# PCB2_1_1.net
KiCad netlist of a schematic drawn in EAGLE
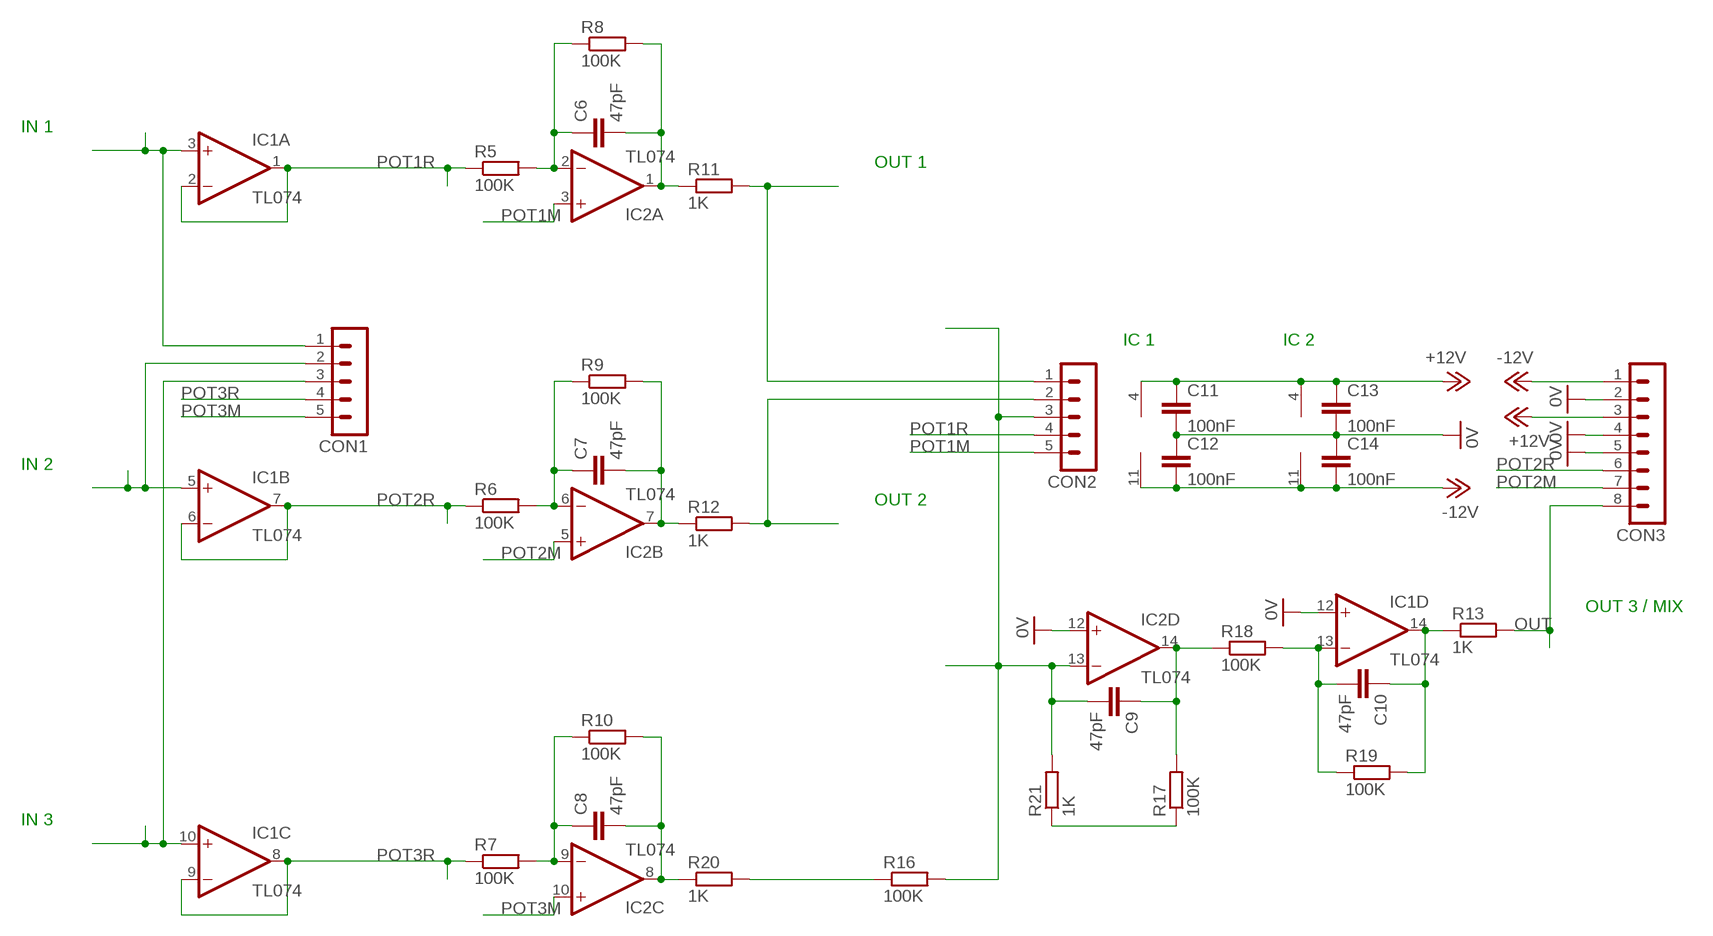
[diagram p0: schematic, sheet 1]

(export (version "E")
  (design (tool "Eeschema 10.0.6"))
  (components
    (comp (ref "C6")
      (value "47pF")
      (footprint "eagle-import:C025-024X044")
      (libsource (lib "eagle-import") (part "C-EU025-024X044"))
    )
    (comp (ref "C7")
      (value "47pF")
      (footprint "eagle-import:C025-024X044")
      (libsource (lib "eagle-import") (part "C-EU025-024X044"))
    )
    (comp (ref "C8")
      (value "47pF")
      (footprint "eagle-import:C025-024X044")
      (libsource (lib "eagle-import") (part "C-EU025-024X044"))
    )
    (comp (ref "C9")
      (value "47pF")
      (footprint "eagle-import:C025-024X044")
      (libsource (lib "eagle-import") (part "C-EU025-024X044"))
    )
    (comp (ref "C10")
      (value "47pF")
      (footprint "eagle-import:C025-024X044")
      (libsource (lib "eagle-import") (part "C-EU025-024X044"))
    )
    (comp (ref "C11")
      (value "100nF")
      (footprint "eagle-import:C025-024X044")
      (libsource (lib "eagle-import") (part "C-EU025-024X044"))
    )
    (comp (ref "C12")
      (value "100nF")
      (footprint "eagle-import:C025-024X044")
      (libsource (lib "eagle-import") (part "C-EU025-024X044"))
    )
    (comp (ref "C13")
      (value "100nF")
      (footprint "eagle-import:C025-024X044")
      (libsource (lib "eagle-import") (part "C-EU025-024X044"))
    )
    (comp (ref "C14")
      (value "100nF")
      (footprint "eagle-import:C025-024X044")
      (libsource (lib "eagle-import") (part "C-EU025-024X044"))
    )
    (comp (ref "CON1")
      (value "MA05-1")
      (footprint "eagle-import:MA05-1")
      (libsource (lib "eagle-import") (part "MA05-1"))
    )
    (comp (ref "CON2")
      (value "MA05-1")
      (footprint "eagle-import:MA05-1")
      (libsource (lib "eagle-import") (part "MA05-1"))
    )
    (comp (ref "CON3")
      (value "MA08-1")
      (footprint "eagle-import:MA08-1")
      (libsource (lib "eagle-import") (part "MA08-1"))
    )
    (comp (ref "IC1")
      (value "TL074")
      (footprint "eagle-import:DIL14")
      (libsource (lib "eagle-import") (part "TL074P"))
    )
    (comp (ref "IC2")
      (value "TL074")
      (footprint "eagle-import:DIL14")
      (libsource (lib "eagle-import") (part "TL074P"))
    )
    (comp (ref "R5")
      (value "100K")
      (footprint "eagle-import:0207_9")
      (libsource (lib "eagle-import") (part "R-EU_0207/10"))
    )
    (comp (ref "R6")
      (value "100K")
      (footprint "eagle-import:0207_9")
      (libsource (lib "eagle-import") (part "R-EU_0207/10"))
    )
    (comp (ref "R7")
      (value "100K")
      (footprint "eagle-import:0207_9")
      (libsource (lib "eagle-import") (part "R-EU_0207/10"))
    )
    (comp (ref "R8")
      (value "100K")
      (footprint "eagle-import:0207_9")
      (libsource (lib "eagle-import") (part "R-EU_0207/10"))
    )
    (comp (ref "R9")
      (value "100K")
      (footprint "eagle-import:0207_9")
      (libsource (lib "eagle-import") (part "R-EU_0207/10"))
    )
    (comp (ref "R10")
      (value "100K")
      (footprint "eagle-import:0207_9")
      (libsource (lib "eagle-import") (part "R-EU_0207/10"))
    )
    (comp (ref "R11")
      (value "1K")
      (footprint "eagle-import:0207_9")
      (libsource (lib "eagle-import") (part "R-EU_0207/10"))
    )
    (comp (ref "R12")
      (value "1K")
      (footprint "eagle-import:0207_9")
      (libsource (lib "eagle-import") (part "R-EU_0207/10"))
    )
    (comp (ref "R13")
      (value "1K")
      (footprint "eagle-import:0207_9")
      (libsource (lib "eagle-import") (part "R-EU_0207/10"))
    )
    (comp (ref "R16")
      (value "100K")
      (footprint "eagle-import:0207_9")
      (libsource (lib "eagle-import") (part "R-EU_0207/10"))
    )
    (comp (ref "R17")
      (value "100K")
      (footprint "eagle-import:0207_9")
      (libsource (lib "eagle-import") (part "R-EU_0207/10"))
    )
    (comp (ref "R18")
      (value "100K")
      (footprint "eagle-import:0207_9")
      (libsource (lib "eagle-import") (part "R-EU_0207/10"))
    )
    (comp (ref "R19")
      (value "100K")
      (footprint "eagle-import:0207_9")
      (libsource (lib "eagle-import") (part "R-EU_0207/10"))
    )
    (comp (ref "R20")
      (value "1K")
      (footprint "eagle-import:0207_9")
      (libsource (lib "eagle-import") (part "R-EU_0207/10"))
    )
    (comp (ref "R21")
      (value "1K")
      (footprint "eagle-import:0207_9")
      (libsource (lib "eagle-import") (part "R-EU_0207/10"))
    )
  )
  (nets
    (net (code "1") (name "+12V") (class "Default")
      (node (ref "C11") (pin "1") (pinfunction "1_1") (pintype "passive"))
      (node (ref "C13") (pin "1") (pinfunction "1_1") (pintype "passive"))
      (node (ref "CON3") (pin "3") (pinfunction "3_3") (pintype "passive"))
      (node (ref "IC1") (pin "4") (pinfunction "V+_4") (pintype "power_in"))
      (node (ref "IC2") (pin "4") (pinfunction "V+_4") (pintype "power_in"))
    )
    (net (code "2") (name "-12V") (class "Default")
      (node (ref "C12") (pin "2") (pinfunction "2_2") (pintype "passive"))
      (node (ref "C14") (pin "2") (pinfunction "2_2") (pintype "passive"))
      (node (ref "CON3") (pin "1") (pinfunction "1_1") (pintype "passive"))
      (node (ref "IC1") (pin "11") (pinfunction "V-_11") (pintype "power_in"))
      (node (ref "IC2") (pin "11") (pinfunction "V-_11") (pintype "power_in"))
    )
    (net (code "3") (name "/OUT") (class "Default")
      (node (ref "CON3") (pin "8") (pinfunction "8_8") (pintype "passive"))
      (node (ref "R13") (pin "2") (pinfunction "2_2") (pintype "passive"))
    )
    (net (code "4") (name "/POT1M") (class "Default")
      (node (ref "CON2") (pin "5") (pinfunction "5_5") (pintype "passive"))
      (node (ref "IC2") (pin "3") (pinfunction "+IN_3") (pintype "input"))
    )
    (net (code "5") (name "/POT1R") (class "Default")
      (node (ref "CON2") (pin "4") (pinfunction "4_4") (pintype "passive"))
      (node (ref "IC1") (pin "1") (pinfunction "OUT_1") (pintype "output"))
      (node (ref "IC1") (pin "2") (pinfunction "-IN_2") (pintype "input"))
      (node (ref "R5") (pin "1") (pinfunction "1_1") (pintype "passive"))
    )
    (net (code "6") (name "/POT2M") (class "Default")
      (node (ref "CON3") (pin "7") (pinfunction "7_7") (pintype "passive"))
      (node (ref "IC2") (pin "5") (pinfunction "+IN_5") (pintype "input"))
    )
    (net (code "7") (name "/POT2R") (class "Default")
      (node (ref "CON3") (pin "6") (pinfunction "6_6") (pintype "passive"))
      (node (ref "IC1") (pin "6") (pinfunction "-IN_6") (pintype "input"))
      (node (ref "IC1") (pin "7") (pinfunction "OUT_7") (pintype "output"))
      (node (ref "R6") (pin "1") (pinfunction "1_1") (pintype "passive"))
    )
    (net (code "8") (name "/POT3M") (class "Default")
      (node (ref "CON1") (pin "5") (pinfunction "5_5") (pintype "passive"))
      (node (ref "IC2") (pin "10") (pinfunction "+IN_10") (pintype "input"))
    )
    (net (code "9") (name "/POT3R") (class "Default")
      (node (ref "CON1") (pin "4") (pinfunction "4_4") (pintype "passive"))
      (node (ref "IC1") (pin "8") (pinfunction "OUT_8") (pintype "output"))
      (node (ref "IC1") (pin "9") (pinfunction "-IN_9") (pintype "input"))
      (node (ref "R7") (pin "1") (pinfunction "1_1") (pintype "passive"))
    )
    (net (code "10") (name "0V") (class "Default")
      (node (ref "C11") (pin "2") (pinfunction "2_2") (pintype "passive"))
      (node (ref "C12") (pin "1") (pinfunction "1_1") (pintype "passive"))
      (node (ref "C13") (pin "2") (pinfunction "2_2") (pintype "passive"))
      (node (ref "C14") (pin "1") (pinfunction "1_1") (pintype "passive"))
      (node (ref "CON3") (pin "2") (pinfunction "2_2") (pintype "passive"))
      (node (ref "CON3") (pin "4") (pinfunction "4_4") (pintype "passive"))
      (node (ref "CON3") (pin "5") (pinfunction "5_5") (pintype "passive"))
      (node (ref "IC1") (pin "12") (pinfunction "+IN_12") (pintype "input"))
      (node (ref "IC2") (pin "12") (pinfunction "+IN_12") (pintype "input"))
    )
    (net (code "11") (name "Net-(CON2-Pad1)") (class "Default")
      (node (ref "CON2") (pin "1") (pinfunction "1_1") (pintype "passive"))
      (node (ref "R11") (pin "2") (pinfunction "2_2") (pintype "passive"))
    )
    (net (code "12") (name "Net-(CON2-Pad2)") (class "Default")
      (node (ref "CON2") (pin "2") (pinfunction "2_2") (pintype "passive"))
      (node (ref "R12") (pin "2") (pinfunction "2_2") (pintype "passive"))
    )
    (net (code "13") (name "Net-(IC1A-+IN)") (class "Default")
      (node (ref "CON1") (pin "1") (pinfunction "1_1") (pintype "passive"))
      (node (ref "IC1") (pin "3") (pinfunction "+IN_3") (pintype "input"))
    )
    (net (code "14") (name "Net-(IC1B-+IN)") (class "Default")
      (node (ref "CON1") (pin "2") (pinfunction "2_2") (pintype "passive"))
      (node (ref "IC1") (pin "5") (pinfunction "+IN_5") (pintype "input"))
    )
    (net (code "15") (name "Net-(IC1C-+IN)") (class "Default")
      (node (ref "CON1") (pin "3") (pinfunction "3_3") (pintype "passive"))
      (node (ref "IC1") (pin "10") (pinfunction "+IN_10") (pintype "input"))
    )
    (net (code "16") (name "Net-(IC1D--IN)") (class "Default")
      (node (ref "C10") (pin "2") (pinfunction "2_2") (pintype "passive"))
      (node (ref "IC1") (pin "13") (pinfunction "-IN_13") (pintype "input"))
      (node (ref "R18") (pin "2") (pinfunction "2_2") (pintype "passive"))
      (node (ref "R19") (pin "1") (pinfunction "1_1") (pintype "passive"))
    )
    (net (code "17") (name "Net-(IC1D-OUT)") (class "Default")
      (node (ref "C10") (pin "1") (pinfunction "1_1") (pintype "passive"))
      (node (ref "IC1") (pin "14") (pinfunction "OUT_14") (pintype "output"))
      (node (ref "R13") (pin "1") (pinfunction "1_1") (pintype "passive"))
      (node (ref "R19") (pin "2") (pinfunction "2_2") (pintype "passive"))
    )
    (net (code "18") (name "Net-(IC2A--IN)") (class "Default")
      (node (ref "C6") (pin "1") (pinfunction "1_1") (pintype "passive"))
      (node (ref "IC2") (pin "2") (pinfunction "-IN_2") (pintype "input"))
      (node (ref "R5") (pin "2") (pinfunction "2_2") (pintype "passive"))
      (node (ref "R8") (pin "1") (pinfunction "1_1") (pintype "passive"))
    )
    (net (code "19") (name "Net-(IC2A-OUT)") (class "Default")
      (node (ref "C6") (pin "2") (pinfunction "2_2") (pintype "passive"))
      (node (ref "IC2") (pin "1") (pinfunction "OUT_1") (pintype "output"))
      (node (ref "R11") (pin "1") (pinfunction "1_1") (pintype "passive"))
      (node (ref "R8") (pin "2") (pinfunction "2_2") (pintype "passive"))
    )
    (net (code "20") (name "Net-(IC2B--IN)") (class "Default")
      (node (ref "C7") (pin "1") (pinfunction "1_1") (pintype "passive"))
      (node (ref "IC2") (pin "6") (pinfunction "-IN_6") (pintype "input"))
      (node (ref "R6") (pin "2") (pinfunction "2_2") (pintype "passive"))
      (node (ref "R9") (pin "1") (pinfunction "1_1") (pintype "passive"))
    )
    (net (code "21") (name "Net-(IC2B-OUT)") (class "Default")
      (node (ref "C7") (pin "2") (pinfunction "2_2") (pintype "passive"))
      (node (ref "IC2") (pin "7") (pinfunction "OUT_7") (pintype "output"))
      (node (ref "R12") (pin "1") (pinfunction "1_1") (pintype "passive"))
      (node (ref "R9") (pin "2") (pinfunction "2_2") (pintype "passive"))
    )
    (net (code "22") (name "Net-(IC2C--IN)") (class "Default")
      (node (ref "C8") (pin "1") (pinfunction "1_1") (pintype "passive"))
      (node (ref "IC2") (pin "9") (pinfunction "-IN_9") (pintype "input"))
      (node (ref "R10") (pin "1") (pinfunction "1_1") (pintype "passive"))
      (node (ref "R7") (pin "2") (pinfunction "2_2") (pintype "passive"))
    )
    (net (code "23") (name "Net-(IC2C-OUT)") (class "Default")
      (node (ref "C8") (pin "2") (pinfunction "2_2") (pintype "passive"))
      (node (ref "IC2") (pin "8") (pinfunction "OUT_8") (pintype "output"))
      (node (ref "R10") (pin "2") (pinfunction "2_2") (pintype "passive"))
      (node (ref "R20") (pin "1") (pinfunction "1_1") (pintype "passive"))
    )
    (net (code "24") (name "Net-(IC2D--IN)") (class "Default")
      (node (ref "C9") (pin "2") (pinfunction "2_2") (pintype "passive"))
      (node (ref "CON2") (pin "3") (pinfunction "3_3") (pintype "passive"))
      (node (ref "IC2") (pin "13") (pinfunction "-IN_13") (pintype "input"))
      (node (ref "R16") (pin "2") (pinfunction "2_2") (pintype "passive"))
      (node (ref "R21") (pin "2") (pinfunction "2_2") (pintype "passive"))
    )
    (net (code "25") (name "Net-(IC2D-OUT)") (class "Default")
      (node (ref "C9") (pin "1") (pinfunction "1_1") (pintype "passive"))
      (node (ref "IC2") (pin "14") (pinfunction "OUT_14") (pintype "output"))
      (node (ref "R17") (pin "2") (pinfunction "2_2") (pintype "passive"))
      (node (ref "R18") (pin "1") (pinfunction "1_1") (pintype "passive"))
    )
    (net (code "26") (name "Net-(R16-Pad1)") (class "Default")
      (node (ref "R16") (pin "1") (pinfunction "1_1") (pintype "passive"))
      (node (ref "R20") (pin "2") (pinfunction "2_2") (pintype "passive"))
    )
    (net (code "27") (name "Net-(R17-Pad1)") (class "Default")
      (node (ref "R17") (pin "1") (pinfunction "1_1") (pintype "passive"))
      (node (ref "R21") (pin "1") (pinfunction "1_1") (pintype "passive"))
    )
  )
)
